# controller2.net
KiCad netlist of a schematic drawn in EAGLE
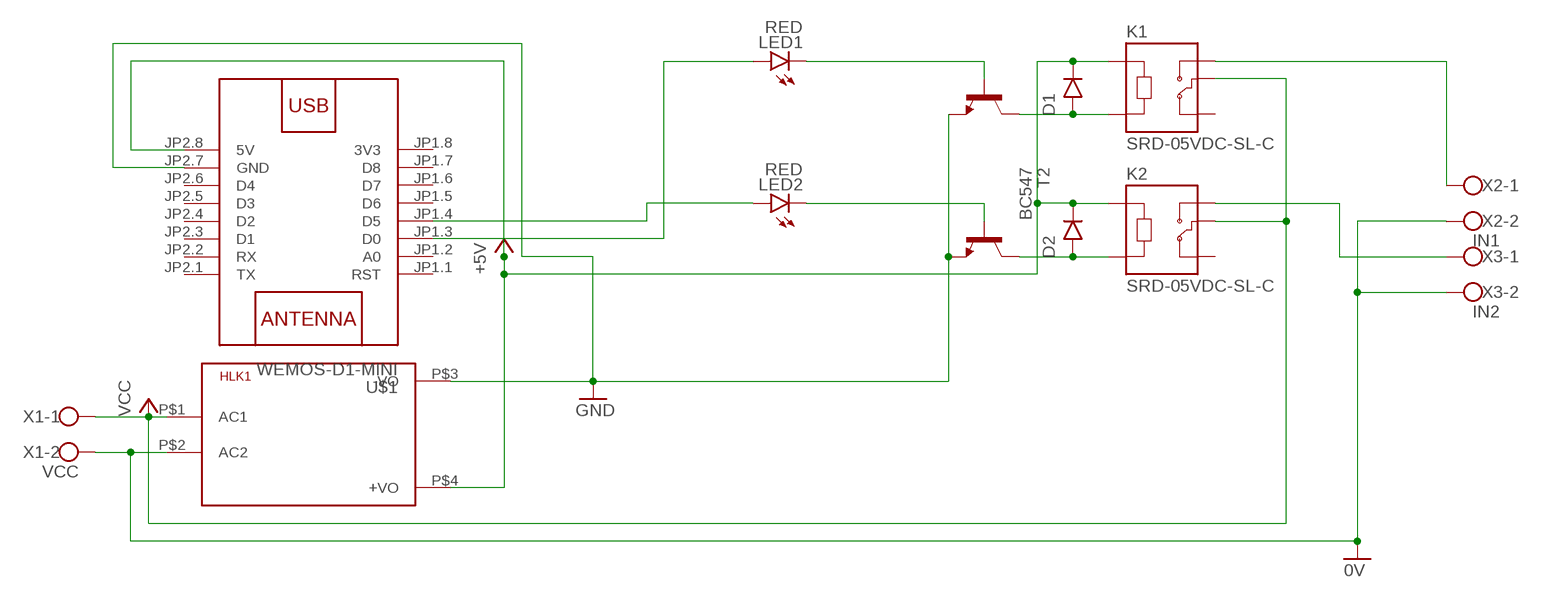
[diagram p0: schematic, sheet 1]

(export (version "E")
  (design (tool "Eeschema 10.0.6"))
  (components
    (comp (ref "D1")
      (value "1N4001")
      (footprint "eagle-import:DO41-10")
      (libsource (lib "eagle-import") (part "1N4001"))
    )
    (comp (ref "D2")
      (value "1N4001")
      (footprint "eagle-import:DO41-10")
      (libsource (lib "eagle-import") (part "1N4001"))
    )
    (comp (ref "HLK1")
      (value "HLK-PM013W")
      (footprint "eagle-import:HLK-PM01")
      (libsource (lib "eagle-import") (part "HLK-PM013W"))
    )
    (comp (ref "K1")
      (value "SRD-05VDC-SL-C")
      (footprint "eagle-import:RELAY_SRD-05VDC-SL-C")
      (fields (field (name "MF") "Songle Relay"))
      (libsource (lib "eagle-import") (part "SRD-05VDC-SL-C"))
    )
    (comp (ref "K2")
      (value "SRD-05VDC-SL-C")
      (footprint "eagle-import:RELAY_SRD-05VDC-SL-C")
      (fields (field (name "MF") "Songle Relay"))
      (libsource (lib "eagle-import") (part "SRD-05VDC-SL-C"))
    )
    (comp (ref "LED1")
      (value "RED")
      (footprint "eagle-import:LED3MM")
      (libsource (lib "eagle-import") (part "LED3MM"))
    )
    (comp (ref "LED2")
      (value "RED")
      (footprint "eagle-import:LED3MM")
      (libsource (lib "eagle-import") (part "LED3MM"))
    )
    (comp (ref "T1")
      (value "BC547")
      (footprint "eagle-import:TO92")
      (libsource (lib "eagle-import") (part "BC547"))
    )
    (comp (ref "T2")
      (value "BC547")
      (footprint "eagle-import:TO92")
      (libsource (lib "eagle-import") (part "BC547"))
    )
    (comp (ref "U$1")
      (value "WEMOS-D1-MINI")
      (footprint "eagle-import:WEMOS-D1-MINI")
      (libsource (lib "eagle-import") (part "WEMOS-D1-MINI"))
    )
    (comp (ref "X1")
      (value "VCC")
      (footprint "eagle-import:W237-102")
      (fields (field (name "MPN") "237-102"))
      (libsource (lib "eagle-import") (part "W237-102"))
    )
    (comp (ref "X2")
      (value "IN1")
      (footprint "eagle-import:W237-102")
      (fields (field (name "MPN") "237-102"))
      (libsource (lib "eagle-import") (part "W237-102"))
    )
    (comp (ref "X3")
      (value "IN2")
      (footprint "eagle-import:W237-102")
      (fields (field (name "MPN") "237-102"))
      (libsource (lib "eagle-import") (part "W237-102"))
    )
  )
  (nets
    (net (code "1") (name "+5V") (class "Default")
      (node (ref "D1") (pin "C") (pinfunction "CATHODE_C") (pintype "passive"))
      (node (ref "D2") (pin "C") (pinfunction "CATHODE_C") (pintype "passive"))
      (node (ref "HLK1") (pin "P$4") (pinfunction "+VO_P$4") (pintype "bidirectional"))
      (node (ref "K1") (pin "A1") (pinfunction "A1_A1") (pintype "passive"))
      (node (ref "K2") (pin "A1") (pinfunction "A1_A1") (pintype "passive"))
      (node (ref "U$1") (pin "JP2.8") (pinfunction "5V_JP2.8") (pintype "power_in"))
    )
    (net (code "2") (name "/3V3") (class "Default")
      (node (ref "U$1") (pin "JP1.8") (pinfunction "3V3_JP1.8") (pintype "power_in"))
    )
    (net (code "3") (name "0V") (class "Default")
      (node (ref "HLK1") (pin "P$2") (pinfunction "AC2_P$2") (pintype "bidirectional"))
      (node (ref "X1") (pin "2") (pinfunction "KL_2") (pintype "passive"))
      (node (ref "X2") (pin "2") (pinfunction "KL_2") (pintype "passive"))
      (node (ref "X3") (pin "2") (pinfunction "KL_2") (pintype "passive"))
    )
    (net (code "4") (name "GND") (class "Default")
      (node (ref "HLK1") (pin "P$3") (pinfunction "-VO_P$3") (pintype "bidirectional"))
      (node (ref "T1") (pin "1") (pinfunction "E_1") (pintype "passive"))
      (node (ref "T2") (pin "1") (pinfunction "E_1") (pintype "passive"))
      (node (ref "U$1") (pin "JP2.7") (pinfunction "GND_JP2.7") (pintype "power_in"))
    )
    (net (code "5") (name "Net-(D1-ANODE)") (class "Default")
      (node (ref "D1") (pin "A") (pinfunction "ANODE_A") (pintype "passive"))
      (node (ref "K1") (pin "A2") (pinfunction "A2_A2") (pintype "passive"))
      (node (ref "T1") (pin "3") (pinfunction "C_3") (pintype "passive"))
    )
    (net (code "6") (name "Net-(D2-ANODE)") (class "Default")
      (node (ref "D2") (pin "A") (pinfunction "ANODE_A") (pintype "passive"))
      (node (ref "K2") (pin "A2") (pinfunction "A2_A2") (pintype "passive"))
      (node (ref "T2") (pin "3") (pinfunction "C_3") (pintype "passive"))
    )
    (net (code "7") (name "Net-(LED1-C)") (class "Default")
      (node (ref "LED1") (pin "K") (pinfunction "C_K") (pintype "passive"))
      (node (ref "T1") (pin "2") (pinfunction "B_2") (pintype "passive"))
    )
    (net (code "8") (name "Net-(LED2-C)") (class "Default")
      (node (ref "LED2") (pin "K") (pinfunction "C_K") (pintype "passive"))
      (node (ref "T2") (pin "2") (pinfunction "B_2") (pintype "passive"))
    )
    (net (code "9") (name "Net-(U$1-D0)") (class "Default")
      (node (ref "LED1") (pin "A") (pinfunction "A_A") (pintype "passive"))
      (node (ref "U$1") (pin "JP1.3") (pinfunction "D0_JP1.3") (pintype "bidirectional"))
    )
    (net (code "10") (name "Net-(U$1-D5)") (class "Default")
      (node (ref "LED2") (pin "A") (pinfunction "A_A") (pintype "passive"))
      (node (ref "U$1") (pin "JP1.4") (pinfunction "D5_JP1.4") (pintype "bidirectional"))
    )
    (net (code "11") (name "Net-(X2A-KL)") (class "Default")
      (node (ref "K1") (pin "NO") (pinfunction "NO_NO") (pintype "passive"))
      (node (ref "X2") (pin "1") (pinfunction "KL_1") (pintype "passive"))
    )
    (net (code "12") (name "Net-(X3A-KL)") (class "Default")
      (node (ref "K2") (pin "NO") (pinfunction "NO_NO") (pintype "passive"))
      (node (ref "X3") (pin "1") (pinfunction "KL_1") (pintype "passive"))
    )
    (net (code "13") (name "VCC") (class "Default")
      (node (ref "HLK1") (pin "P$1") (pinfunction "AC1_P$1") (pintype "bidirectional"))
      (node (ref "K1") (pin "COM") (pinfunction "COM_COM") (pintype "passive"))
      (node (ref "K2") (pin "COM") (pinfunction "COM_COM") (pintype "passive"))
      (node (ref "X1") (pin "1") (pinfunction "KL_1") (pintype "passive"))
    )
    (net (code "14") (name "unconnected-(K1-PadNC)") (class "Default")
      (node (ref "K1") (pin "NC") (pinfunction "NC_NC") (pintype "passive"))
    )
    (net (code "15") (name "unconnected-(K2-PadNC)") (class "Default")
      (node (ref "K2") (pin "NC") (pinfunction "NC_NC") (pintype "passive"))
    )
    (net (code "16") (name "unconnected-(U$1-A0-PadJP1.2)") (class "Default")
      (node (ref "U$1") (pin "JP1.2") (pinfunction "A0_JP1.2") (pintype "bidirectional"))
    )
    (net (code "17") (name "unconnected-(U$1-D1-PadJP2.3)") (class "Default")
      (node (ref "U$1") (pin "JP2.3") (pinfunction "D1_JP2.3") (pintype "bidirectional"))
    )
    (net (code "18") (name "unconnected-(U$1-D2-PadJP2.4)") (class "Default")
      (node (ref "U$1") (pin "JP2.4") (pinfunction "D2_JP2.4") (pintype "bidirectional"))
    )
    (net (code "19") (name "unconnected-(U$1-D3-PadJP2.5)") (class "Default")
      (node (ref "U$1") (pin "JP2.5") (pinfunction "D3_JP2.5") (pintype "bidirectional"))
    )
    (net (code "20") (name "unconnected-(U$1-D4-PadJP2.6)") (class "Default")
      (node (ref "U$1") (pin "JP2.6") (pinfunction "D4_JP2.6") (pintype "bidirectional"))
    )
    (net (code "21") (name "unconnected-(U$1-D6-PadJP1.5)") (class "Default")
      (node (ref "U$1") (pin "JP1.5") (pinfunction "D6_JP1.5") (pintype "bidirectional"))
    )
    (net (code "22") (name "unconnected-(U$1-D7-PadJP1.6)") (class "Default")
      (node (ref "U$1") (pin "JP1.6") (pinfunction "D7_JP1.6") (pintype "bidirectional"))
    )
    (net (code "23") (name "unconnected-(U$1-D8-PadJP1.7)") (class "Default")
      (node (ref "U$1") (pin "JP1.7") (pinfunction "D8_JP1.7") (pintype "bidirectional"))
    )
    (net (code "24") (name "unconnected-(U$1-RST-PadJP1.1)") (class "Default")
      (node (ref "U$1") (pin "JP1.1") (pinfunction "RST_JP1.1") (pintype "bidirectional"))
    )
    (net (code "25") (name "unconnected-(U$1-RX-PadJP2.2)") (class "Default")
      (node (ref "U$1") (pin "JP2.2") (pinfunction "RX_JP2.2") (pintype "bidirectional"))
    )
    (net (code "26") (name "unconnected-(U$1-TX-PadJP2.1)") (class "Default")
      (node (ref "U$1") (pin "JP2.1") (pinfunction "TX_JP2.1") (pintype "bidirectional"))
    )
  )
)
